# 05_MISC.net
KiCad netlist of a schematic drawn in Altium Designer
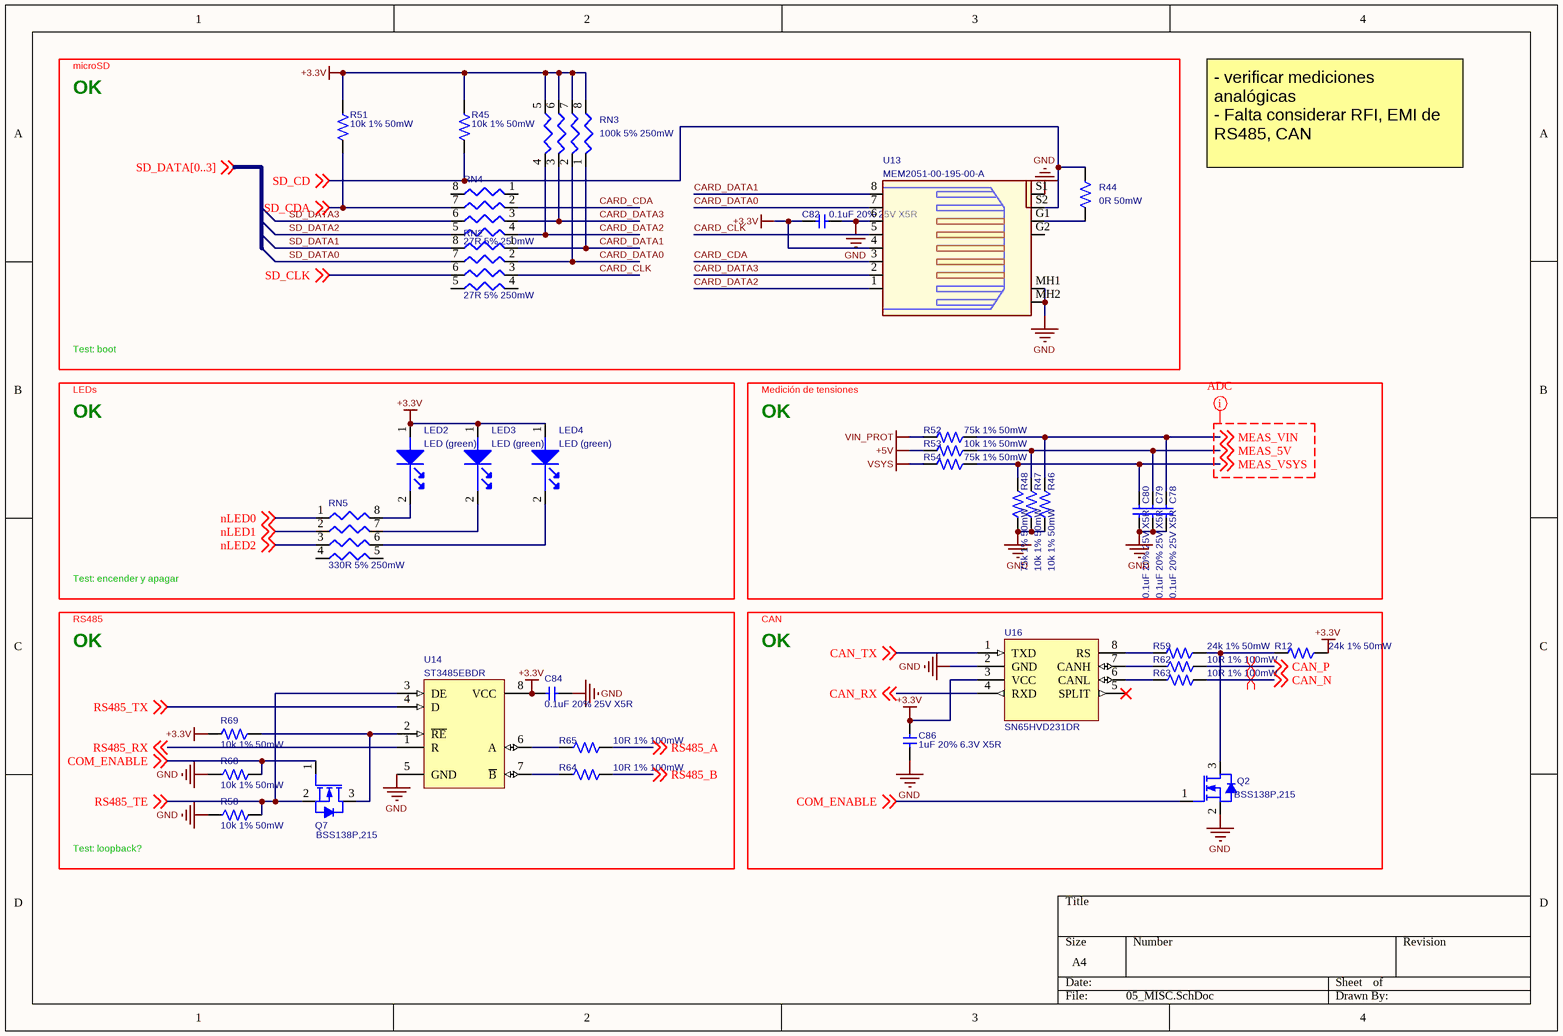
[diagram p0: 05_MISC.SchDoc]

(export (version "E")
  (design (tool "Eeschema 10.0.6"))
  (components
    (comp (ref "C78")
      (value "0.1uF 20% 25V X5R")
      (footprint "CAPC1005N")
      (description "Capacitor, Ceramic")
      (fields
        (field (name "MFG") "SAMSUNG")
        (field (name "TOLERANCE") "20%")
        (field (name "FOOTPRINT CHECKED") "Assign OK, Footprint OK")
      )
      (libsource (lib "*") (part "C_Dup1"))
    )
    (comp (ref "C79")
      (value "0.1uF 20% 25V X5R")
      (footprint "CAPC1005N")
      (description "Capacitor, Ceramic")
      (fields
        (field (name "MFG") "SAMSUNG")
        (field (name "TOLERANCE") "20%")
        (field (name "FOOTPRINT CHECKED") "Assign OK, Footprint OK")
      )
      (libsource (lib "*") (part "C_Dup1"))
    )
    (comp (ref "C80")
      (value "0.1uF 20% 25V X5R")
      (footprint "CAPC1005N")
      (description "Capacitor, Ceramic")
      (fields
        (field (name "MFG") "SAMSUNG")
        (field (name "TOLERANCE") "20%")
        (field (name "FOOTPRINT CHECKED") "Assign OK, Footprint OK")
      )
      (libsource (lib "*") (part "C_Dup1"))
    )
    (comp (ref "C82")
      (value "0.1uF 20% 25V X5R")
      (footprint "CAPC1005N")
      (description "Capacitor, Ceramic")
      (fields
        (field (name "MFG") "SAMSUNG")
        (field (name "TOLERANCE") "20%")
        (field (name "FOOTPRINT CHECKED") "Assign OK, Footprint OK")
      )
      (libsource (lib "*") (part "C_Dup1"))
    )
    (comp (ref "C84")
      (value "0.1uF 20% 25V X5R")
      (footprint "CAPC1005N")
      (description "Capacitor, Ceramic")
      (fields
        (field (name "MFG") "SAMSUNG")
        (field (name "TOLERANCE") "20%")
        (field (name "FOOTPRINT CHECKED") "Assign OK, Footprint OK")
      )
      (libsource (lib "*") (part "C_Dup1"))
    )
    (comp (ref "C86")
      (value "1uF 20% 6.3V X5R")
      (footprint "CAPC1005N")
      (description "Capacitor, Ceramic")
      (fields
        (field (name "MFG") "SAMSUNG")
        (field (name "TOLERANCE") "20%")
        (field (name "FOOTPRINT CHECKED") "Assign OK, Footprint OK")
      )
      (libsource (lib "*") (part "C_Dup1"))
    )
    (comp (ref "LED2")
      (value "LED (green)")
      (footprint "LEDC1608N")
      (description "LED")
      (fields (field (name "MFG") "<GENERIC>") (field (name "FOOTPRINT CHECKED") "Assign OK, Footprint OK"))
      (libsource (lib "*") (part "Led Red HSMC-C170"))
    )
    (comp (ref "LED3")
      (value "LED (green)")
      (footprint "LEDC1608N")
      (description "LED")
      (fields (field (name "MFG") "<GENERIC>") (field (name "FOOTPRINT CHECKED") "Assign OK, Footprint OK"))
      (libsource (lib "*") (part "Led Red HSMC-C170"))
    )
    (comp (ref "LED4")
      (value "LED (green)")
      (footprint "LEDC1608N")
      (description "LED")
      (fields (field (name "MFG") "<GENERIC>") (field (name "FOOTPRINT CHECKED") "Assign OK, Footprint OK"))
      (libsource (lib "*") (part "Led Red HSMC-C170"))
    )
    (comp (ref "Q2")
      (value "BSS138P,215")
      (footprint "SOT95P230X110-3N")
      (description "MOSFET, N channel")
      (fields (field (name "MFG") "NXP") (field (name "FOOTPRINT CHECKED") "Assign OK, Footprint OK"))
      (libsource (lib "MCHP-CDB") (part "Transistor MOS-N GSD"))
    )
    (comp (ref "Q7")
      (value "BSS138P,215")
      (footprint "SOT95P230X110-3N")
      (description "MOSFET, N channel")
      (fields (field (name "MFG") "NXP") (field (name "FOOTPRINT CHECKED") "Assign OK, Footprint OK"))
      (libsource (lib "MCHP-CDB") (part "Transistor MOS-N GSD"))
    )
    (comp (ref "R12")
      (value "24k 1% 50mW")
      (footprint "RESC1005X40N")
      (description "Resistor, SMD")
      (fields
        (field (name "MFG") "<GENERIC>")
        (field (name "POWER") "50mW")
        (field (name "FOOTPRINT CHECKED") "Assign OK, Footprint OK")
      )
      (libsource (lib "*") (part "R"))
    )
    (comp (ref "R44")
      (value "0R 50mW")
      (footprint "RESC1005X40N")
      (description "Resistor, SMD")
      (fields
        (field (name "MFG") "<GENERIC>")
        (field (name "POWER") "50mW")
        (field (name "FOOTPRINT CHECKED") "Assign OK, Footprint OK")
      )
      (libsource (lib "*") (part "R"))
    )
    (comp (ref "R45")
      (value "10k 1% 50mW")
      (footprint "RESC1005X40N")
      (description "Resistor, SMD")
      (fields
        (field (name "MFG") "<GENERIC>")
        (field (name "POWER") "50mW")
        (field (name "FOOTPRINT CHECKED") "Assign OK, Footprint OK")
      )
      (libsource (lib "*") (part "R"))
    )
    (comp (ref "R46")
      (value "10k 1% 50mW")
      (footprint "RESC1005X40N")
      (description "Resistor, SMD")
      (fields
        (field (name "MFG") "<GENERIC>")
        (field (name "POWER") "50mW")
        (field (name "FOOTPRINT CHECKED") "Assign OK, Footprint OK")
      )
      (libsource (lib "*") (part "R"))
    )
    (comp (ref "R47")
      (value "10k 1% 50mW")
      (footprint "RESC1005X40N")
      (description "Resistor, SMD")
      (fields
        (field (name "MFG") "<GENERIC>")
        (field (name "POWER") "50mW")
        (field (name "FOOTPRINT CHECKED") "Assign OK, Footprint OK")
      )
      (libsource (lib "*") (part "R"))
    )
    (comp (ref "R48")
      (value "75k 1% 50mW")
      (footprint "RESC1005X40N")
      (description "Resistor, SMD")
      (fields
        (field (name "MFG") "<GENERIC>")
        (field (name "POWER") "50mW")
        (field (name "FOOTPRINT CHECKED") "Assign OK, Footprint OK")
      )
      (libsource (lib "*") (part "R"))
    )
    (comp (ref "R51")
      (value "10k 1% 50mW")
      (footprint "RESC1005X40N")
      (description "Resistor, SMD")
      (fields
        (field (name "MFG") "<GENERIC>")
        (field (name "POWER") "50mW")
        (field (name "FOOTPRINT CHECKED") "Assign OK, Footprint OK")
      )
      (libsource (lib "*") (part "R"))
    )
    (comp (ref "R52")
      (value "75k 1% 50mW")
      (footprint "RESC1005X40N")
      (description "Resistor, SMD")
      (fields
        (field (name "MFG") "<GENERIC>")
        (field (name "POWER") "50mW")
        (field (name "FOOTPRINT CHECKED") "Assign OK, Footprint OK")
      )
      (libsource (lib "*") (part "R"))
    )
    (comp (ref "R53")
      (value "10k 1% 50mW")
      (footprint "RESC1005X40N")
      (description "Resistor, SMD")
      (fields
        (field (name "MFG") "<GENERIC>")
        (field (name "POWER") "50mW")
        (field (name "FOOTPRINT CHECKED") "Assign OK, Footprint OK")
      )
      (libsource (lib "*") (part "R"))
    )
    (comp (ref "R54")
      (value "75k 1% 50mW")
      (footprint "RESC1005X40N")
      (description "Resistor, SMD")
      (fields
        (field (name "MFG") "<GENERIC>")
        (field (name "POWER") "50mW")
        (field (name "FOOTPRINT CHECKED") "Assign OK, Footprint OK")
      )
      (libsource (lib "*") (part "R"))
    )
    (comp (ref "R58")
      (value "10k 1% 50mW")
      (footprint "RESC1005X40N")
      (description "Resistor, SMD")
      (fields
        (field (name "MFG") "<GENERIC>")
        (field (name "POWER") "50mW")
        (field (name "FOOTPRINT CHECKED") "Assign OK, Footprint OK")
      )
      (libsource (lib "*") (part "R"))
    )
    (comp (ref "R59")
      (value "24k 1% 50mW")
      (footprint "RESC1005X40N")
      (description "Resistor, SMD")
      (fields
        (field (name "MFG") "<GENERIC>")
        (field (name "POWER") "50mW")
        (field (name "FOOTPRINT CHECKED") "Assign OK, Footprint OK")
      )
      (libsource (lib "*") (part "R"))
    )
    (comp (ref "R62")
      (value "10R 1% 100mW")
      (footprint "RESC1608X40N")
      (description "Resistor, SMD")
      (fields
        (field (name "MFG") "<GENERIC>")
        (field (name "POWER") "100mW")
        (field (name "FOOTPRINT CHECKED") "Assign OK, Footprint OK")
      )
      (libsource (lib "*") (part "R"))
    )
    (comp (ref "R63")
      (value "10R 1% 100mW")
      (footprint "RESC1608X40N")
      (description "Resistor, SMD")
      (fields
        (field (name "MFG") "<GENERIC>")
        (field (name "POWER") "100mW")
        (field (name "FOOTPRINT CHECKED") "Assign OK, Footprint OK")
      )
      (libsource (lib "*") (part "R"))
    )
    (comp (ref "R64")
      (value "10R 1% 100mW")
      (footprint "RESC1608X40N")
      (description "Resistor, SMD")
      (fields
        (field (name "MFG") "<GENERIC>")
        (field (name "POWER") "100mW")
        (field (name "FOOTPRINT CHECKED") "Assign OK, Footprint OK")
      )
      (libsource (lib "*") (part "R"))
    )
    (comp (ref "R65")
      (value "10R 1% 100mW")
      (footprint "RESC1608X40N")
      (description "Resistor, SMD")
      (fields
        (field (name "MFG") "<GENERIC>")
        (field (name "POWER") "100mW")
        (field (name "FOOTPRINT CHECKED") "Assign OK, Footprint OK")
      )
      (libsource (lib "*") (part "R"))
    )
    (comp (ref "R68")
      (value "10k 1% 50mW")
      (footprint "RESC1005X40N")
      (description "Resistor, SMD")
      (fields
        (field (name "MFG") "<GENERIC>")
        (field (name "POWER") "50mW")
        (field (name "FOOTPRINT CHECKED") "Assign OK, Footprint OK")
      )
      (libsource (lib "*") (part "R"))
    )
    (comp (ref "R69")
      (value "10k 1% 50mW")
      (footprint "RESC1005X40N")
      (description "Resistor, SMD")
      (fields
        (field (name "MFG") "<GENERIC>")
        (field (name "POWER") "50mW")
        (field (name "FOOTPRINT CHECKED") "Assign OK, Footprint OK")
      )
      (libsource (lib "*") (part "R"))
    )
    (comp (ref "RN2")
      (value "27R 5% 250mW")
      (footprint "YC164")
      (description "Resistor array")
      (fields
        (field (name "MFG") "<GENERIC>")
        (field (name "POWER") "250mW")
        (field (name "FOOTPRINT CHECKED") "Assign OK, Footprint OK")
      )
      (libsource (lib "*") (part "RESNW_IS_0"))
    )
    (comp (ref "RN3")
      (value "100k 5% 250mW")
      (footprint "YC164")
      (description "Resistor array")
      (fields
        (field (name "MFG") "<GENERIC>")
        (field (name "POWER") "250mW")
        (field (name "FOOTPRINT CHECKED") "Assign OK, Footprint OK")
      )
      (libsource (lib "") (part "RESNW_IS_0_1"))
    )
    (comp (ref "RN4")
      (value "27R 5% 250mW")
      (footprint "YC164")
      (description "Resistor array")
      (fields
        (field (name "MFG") "<GENERIC>")
        (field (name "POWER") "250mW")
        (field (name "FOOTPRINT CHECKED") "Assign OK, Footprint OK")
      )
      (libsource (lib "*") (part "RESNW_IS_0"))
    )
    (comp (ref "RN5")
      (value "330R 5% 250mW")
      (footprint "YC164")
      (description "Resistor array")
      (fields
        (field (name "MFG") "<GENERIC>")
        (field (name "POWER") "250mW")
        (field (name "FOOTPRINT CHECKED") "Assign OK, Footprint OK")
      )
      (libsource (lib "*") (part "RESNW_IS_0"))
    )
    (comp (ref "U13")
      (value "MEM2051-00-195-00-A")
      (footprint "101-00660-68-6+MEM2051-00-195-00-A_revC")
      (description "microSD socket")
      (fields (field (name "MFG") "GCT") (field (name "FOOTPRINT CHECKED") "Assign OK, Footprint OK"))
      (libsource (lib "traz") (part "112A-TAAR-R03"))
    )
    (comp (ref "U14")
      (value "ST3485EBDR")
      (footprint "SOIC127P600X175-8N")
      (description "Differential Bus Transceiver")
      (fields (field (name "MFG") "ST") (field (name "FOOTPRINT CHECKED") "Assign OK, Footprint OK"))
      (libsource (lib "TI Interface Line Transceiver") (part "SN75176BD"))
    )
    (comp (ref "U16")
      (value "SN65HVD231DR")
      (footprint "SOIC127P600X175-8N")
      (description "High speed CAN transceiver")
      (fields (field (name "MFG") "TI") (field (name "FOOTPRINT CHECKED") "Assign OK, Footprint OK"))
      (libsource (lib "traz") (part "TJA1042TK/3"))
    )
  )
  (nets
    (net (code "1") (name "+3.3V") (class "Default")
      (node (ref "C82") (pin "1") (pinfunction "1_1") (pintype "passive"))
      (node (ref "C84") (pin "1") (pinfunction "1_1") (pintype "passive"))
      (node (ref "C86") (pin "1") (pinfunction "1_1") (pintype "passive"))
      (node (ref "LED2") (pin "1") (pinfunction "CATHODE_1") (pintype "passive"))
      (node (ref "LED3") (pin "1") (pinfunction "CATHODE_1") (pintype "passive"))
      (node (ref "LED4") (pin "1") (pinfunction "CATHODE_1") (pintype "passive"))
      (node (ref "R12") (pin "1") (pinfunction "1_1") (pintype "passive"))
      (node (ref "R45") (pin "1") (pinfunction "1_1") (pintype "passive"))
      (node (ref "R51") (pin "1") (pinfunction "1_1") (pintype "passive"))
      (node (ref "R69") (pin "2") (pinfunction "2_2") (pintype "passive"))
      (node (ref "RN3") (pin "5") (pinfunction "5_5") (pintype "passive"))
      (node (ref "RN3") (pin "6") (pinfunction "6_6") (pintype "passive"))
      (node (ref "RN3") (pin "7") (pinfunction "7_7") (pintype "passive"))
      (node (ref "RN3") (pin "8") (pinfunction "8_8") (pintype "passive"))
      (node (ref "U13") (pin "4") (pinfunction "4_4") (pintype "passive"))
      (node (ref "U14") (pin "8") (pinfunction "VCC_8") (pintype "power_in"))
      (node (ref "U16") (pin "3") (pinfunction "VCC_3") (pintype "power_in"))
    )
    (net (code "2") (name "+5V") (class "Default")
      (node (ref "R53") (pin "2") (pinfunction "2_2") (pintype "passive"))
    )
    (net (code "3") (name "/CARD_CDA") (class "Default")
      (node (ref "RN4") (pin "2") (pinfunction "2_2") (pintype "passive"))
      (node (ref "U13") (pin "3") (pinfunction "3_3") (pintype "passive"))
    )
    (net (code "4") (name "/CARD_CLK") (class "Default")
      (node (ref "RN2") (pin "3") (pinfunction "3_3") (pintype "passive"))
      (node (ref "U13") (pin "5") (pinfunction "5_5") (pintype "passive"))
    )
    (net (code "5") (name "/CARD_DATA0") (class "Default")
      (node (ref "RN2") (pin "2") (pinfunction "2_2") (pintype "passive"))
      (node (ref "RN3") (pin "2") (pinfunction "2_2") (pintype "passive"))
      (node (ref "U13") (pin "7") (pinfunction "7_7") (pintype "passive"))
    )
    (net (code "6") (name "/CARD_DATA1") (class "Default")
      (node (ref "RN2") (pin "1") (pinfunction "1_1") (pintype "passive"))
      (node (ref "RN3") (pin "1") (pinfunction "1_1") (pintype "passive"))
      (node (ref "U13") (pin "8") (pinfunction "8_8") (pintype "passive"))
    )
    (net (code "7") (name "/CARD_DATA2") (class "Default")
      (node (ref "RN3") (pin "4") (pinfunction "4_4") (pintype "passive"))
      (node (ref "RN4") (pin "4") (pinfunction "4_4") (pintype "passive"))
      (node (ref "U13") (pin "1") (pinfunction "1_1") (pintype "passive"))
    )
    (net (code "8") (name "/CARD_DATA3") (class "Default")
      (node (ref "RN3") (pin "3") (pinfunction "3_3") (pintype "passive"))
      (node (ref "RN4") (pin "3") (pinfunction "3_3") (pintype "passive"))
      (node (ref "U13") (pin "2") (pinfunction "2_2") (pintype "passive"))
    )
    (net (code "9") (name "CAN_N") (class "Default")
      (node (ref "R63") (pin "2") (pinfunction "2_2") (pintype "passive"))
    )
    (net (code "10") (name "CAN_P") (class "Default")
      (node (ref "R62") (pin "2") (pinfunction "2_2") (pintype "passive"))
    )
    (net (code "11") (name "CAN_RX") (class "Default")
      (node (ref "U16") (pin "4") (pinfunction "RXD_4") (pintype "output"))
    )
    (net (code "12") (name "CAN_TX") (class "Default")
      (node (ref "U16") (pin "1") (pinfunction "TXD_1") (pintype "input"))
    )
    (net (code "13") (name "COM_ENABLE") (class "Default")
      (node (ref "Q2") (pin "1") (pinfunction "G_1") (pintype "passive"))
      (node (ref "Q7") (pin "1") (pinfunction "G_1") (pintype "passive"))
      (node (ref "R68") (pin "2") (pinfunction "2_2") (pintype "passive"))
    )
    (net (code "14") (name "GND") (class "Default")
      (node (ref "C78") (pin "1") (pinfunction "1_1") (pintype "passive"))
      (node (ref "C79") (pin "1") (pinfunction "1_1") (pintype "passive"))
      (node (ref "C80") (pin "1") (pinfunction "1_1") (pintype "passive"))
      (node (ref "C82") (pin "2") (pinfunction "2_2") (pintype "passive"))
      (node (ref "C84") (pin "2") (pinfunction "2_2") (pintype "passive"))
      (node (ref "C86") (pin "2") (pinfunction "2_2") (pintype "passive"))
      (node (ref "Q2") (pin "2") (pinfunction "S_2") (pintype "passive"))
      (node (ref "R46") (pin "1") (pinfunction "1_1") (pintype "passive"))
      (node (ref "R47") (pin "1") (pinfunction "1_1") (pintype "passive"))
      (node (ref "R48") (pin "1") (pinfunction "1_1") (pintype "passive"))
      (node (ref "R58") (pin "1") (pinfunction "1_1") (pintype "passive"))
      (node (ref "R68") (pin "1") (pinfunction "1_1") (pintype "passive"))
      (node (ref "U13") (pin "6") (pinfunction "6_6") (pintype "passive"))
      (node (ref "U13") (pin "MH1") (pinfunction "MH1_MH1") (pintype "passive"))
      (node (ref "U13") (pin "MH2") (pinfunction "MH2_MH2") (pintype "passive"))
      (node (ref "U13") (pin "S1") (pinfunction "S1_S1") (pintype "passive"))
      (node (ref "U14") (pin "5") (pinfunction "GND_5") (pintype "power_in"))
      (node (ref "U16") (pin "2") (pinfunction "GND_2") (pintype "power_in"))
    )
    (net (code "15") (name "MEAS_5V") (class "Default")
      (node (ref "C79") (pin "2") (pinfunction "2_2") (pintype "passive"))
      (node (ref "R47") (pin "2") (pinfunction "2_2") (pintype "passive"))
      (node (ref "R53") (pin "1") (pinfunction "1_1") (pintype "passive"))
    )
    (net (code "16") (name "MEAS_VIN") (class "Default")
      (node (ref "C78") (pin "2") (pinfunction "2_2") (pintype "passive"))
      (node (ref "R46") (pin "2") (pinfunction "2_2") (pintype "passive"))
      (node (ref "R52") (pin "1") (pinfunction "1_1") (pintype "passive"))
    )
    (net (code "17") (name "MEAS_VSYS") (class "Default")
      (node (ref "C80") (pin "2") (pinfunction "2_2") (pintype "passive"))
      (node (ref "R48") (pin "2") (pinfunction "2_2") (pintype "passive"))
      (node (ref "R54") (pin "1") (pinfunction "1_1") (pintype "passive"))
    )
    (net (code "18") (name "Net-(LED2-ANODE)") (class "Default")
      (node (ref "LED2") (pin "2") (pinfunction "ANODE_2") (pintype "passive"))
      (node (ref "RN5") (pin "8") (pinfunction "8_8") (pintype "passive"))
    )
    (net (code "19") (name "Net-(LED3-ANODE)") (class "Default")
      (node (ref "LED3") (pin "2") (pinfunction "ANODE_2") (pintype "passive"))
      (node (ref "RN5") (pin "7") (pinfunction "7_7") (pintype "passive"))
    )
    (net (code "20") (name "Net-(LED4-ANODE)") (class "Default")
      (node (ref "LED4") (pin "2") (pinfunction "ANODE_2") (pintype "passive"))
      (node (ref "RN5") (pin "6") (pinfunction "6_6") (pintype "passive"))
    )
    (net (code "21") (name "Net-(Q2-D)") (class "Default")
      (node (ref "Q2") (pin "3") (pinfunction "D_3") (pintype "passive"))
      (node (ref "R12") (pin "2") (pinfunction "2_2") (pintype "passive"))
      (node (ref "R59") (pin "1") (pinfunction "1_1") (pintype "passive"))
    )
    (net (code "22") (name "Net-(Q7-D)") (class "Default")
      (node (ref "Q7") (pin "3") (pinfunction "D_3") (pintype "passive"))
      (node (ref "R69") (pin "1") (pinfunction "1_1") (pintype "passive"))
      (node (ref "U14") (pin "2") (pinfunction "~{RE}_2") (pintype "input"))
    )
    (net (code "23") (name "Net-(R44-Pad2)") (class "Default")
      (node (ref "R44") (pin "2") (pinfunction "2_2") (pintype "passive"))
      (node (ref "U13") (pin "G1") (pinfunction "G1_G1") (pintype "passive"))
    )
    (net (code "24") (name "Net-(U14-A)") (class "Default")
      (node (ref "R65") (pin "1") (pinfunction "1_1") (pintype "passive"))
      (node (ref "U14") (pin "6") (pinfunction "A_6") (pintype "bidirectional"))
    )
    (net (code "25") (name "Net-(U14-~{B})") (class "Default")
      (node (ref "R64") (pin "1") (pinfunction "1_1") (pintype "passive"))
      (node (ref "U14") (pin "7") (pinfunction "~{B}_7") (pintype "bidirectional"))
    )
    (net (code "26") (name "Net-(U16-CANH)") (class "Default")
      (node (ref "R62") (pin "1") (pinfunction "1_1") (pintype "passive"))
      (node (ref "U16") (pin "7") (pinfunction "CANH_7") (pintype "bidirectional"))
    )
    (net (code "27") (name "Net-(U16-CANL)") (class "Default")
      (node (ref "R63") (pin "1") (pinfunction "1_1") (pintype "passive"))
      (node (ref "U16") (pin "6") (pinfunction "CANL_6") (pintype "bidirectional"))
    )
    (net (code "28") (name "Net-(U16-RS)") (class "Default")
      (node (ref "R59") (pin "2") (pinfunction "2_2") (pintype "passive"))
      (node (ref "U16") (pin "8") (pinfunction "RS_8") (pintype "passive"))
    )
    (net (code "29") (name "RS485_A") (class "Default")
      (node (ref "R65") (pin "2") (pinfunction "2_2") (pintype "passive"))
    )
    (net (code "30") (name "RS485_B") (class "Default")
      (node (ref "R64") (pin "2") (pinfunction "2_2") (pintype "passive"))
    )
    (net (code "31") (name "RS485_RX") (class "Default")
      (node (ref "U14") (pin "1") (pinfunction "R_1") (pintype "tri_state"))
    )
    (net (code "32") (name "RS485_TE") (class "Default")
      (node (ref "Q7") (pin "2") (pinfunction "S_2") (pintype "passive"))
      (node (ref "R58") (pin "2") (pinfunction "2_2") (pintype "passive"))
      (node (ref "U14") (pin "3") (pinfunction "DE_3") (pintype "input"))
    )
    (net (code "33") (name "RS485_TX") (class "Default")
      (node (ref "U14") (pin "4") (pinfunction "D_4") (pintype "input"))
    )
    (net (code "34") (name "SD_CD") (class "Default")
      (node (ref "R44") (pin "1") (pinfunction "1_1") (pintype "passive"))
      (node (ref "R45") (pin "2") (pinfunction "2_2") (pintype "passive"))
      (node (ref "U13") (pin "S2") (pinfunction "S2_S2") (pintype "passive"))
    )
    (net (code "35") (name "SD_CDA") (class "Default")
      (node (ref "R51") (pin "2") (pinfunction "2_2") (pintype "passive"))
      (node (ref "RN4") (pin "7") (pinfunction "7_7") (pintype "passive"))
    )
    (net (code "36") (name "SD_CLK") (class "Default")
      (node (ref "RN2") (pin "6") (pinfunction "6_6") (pintype "passive"))
    )
    (net (code "37") (name "SD_DATA0") (class "Default")
      (node (ref "RN2") (pin "7") (pinfunction "7_7") (pintype "passive"))
    )
    (net (code "38") (name "SD_DATA1") (class "Default")
      (node (ref "RN2") (pin "8") (pinfunction "8_8") (pintype "passive"))
    )
    (net (code "39") (name "SD_DATA2") (class "Default")
      (node (ref "RN4") (pin "5") (pinfunction "5_5") (pintype "passive"))
    )
    (net (code "40") (name "SD_DATA3") (class "Default")
      (node (ref "RN4") (pin "6") (pinfunction "6_6") (pintype "passive"))
    )
    (net (code "42") (name "VIN_PROT") (class "Default")
      (node (ref "R52") (pin "2") (pinfunction "2_2") (pintype "passive"))
    )
    (net (code "43") (name "VSYS") (class "Default")
      (node (ref "R54") (pin "2") (pinfunction "2_2") (pintype "passive"))
    )
    (net (code "44") (name "nLED0") (class "Default")
      (node (ref "RN5") (pin "1") (pinfunction "1_1") (pintype "passive"))
    )
    (net (code "45") (name "nLED1") (class "Default")
      (node (ref "RN5") (pin "2") (pinfunction "2_2") (pintype "passive"))
    )
    (net (code "46") (name "nLED2") (class "Default")
      (node (ref "RN5") (pin "3") (pinfunction "3_3") (pintype "passive"))
    )
    (net (code "47") (name "unconnected-(RN2-Pad4)") (class "Default")
      (node (ref "RN2") (pin "4") (pinfunction "4_4") (pintype "passive"))
    )
    (net (code "48") (name "unconnected-(RN2-Pad5)") (class "Default")
      (node (ref "RN2") (pin "5") (pinfunction "5_5") (pintype "passive"))
    )
    (net (code "49") (name "unconnected-(RN4-Pad1)") (class "Default")
      (node (ref "RN4") (pin "1") (pinfunction "1_1") (pintype "passive"))
    )
    (net (code "50") (name "unconnected-(RN4-Pad8)") (class "Default")
      (node (ref "RN4") (pin "8") (pinfunction "8_8") (pintype "passive"))
    )
    (net (code "51") (name "unconnected-(RN5-Pad4)") (class "Default")
      (node (ref "RN5") (pin "4") (pinfunction "4_4") (pintype "passive"))
    )
    (net (code "52") (name "unconnected-(RN5-Pad5)") (class "Default")
      (node (ref "RN5") (pin "5") (pinfunction "5_5") (pintype "passive"))
    )
    (net (code "53") (name "unconnected-(U13-PadG2)") (class "Default")
      (node (ref "U13") (pin "G2") (pinfunction "G2_G2") (pintype "passive"))
    )
    (net (code "54") (name "unconnected-(U16-SPLIT-Pad5)") (class "Default")
      (node (ref "U16") (pin "5") (pinfunction "SPLIT_5") (pintype "output+no_connect"))
    )
  )
)
